# fretscanner4.net
KiCad netlist of a schematic drawn in EAGLE
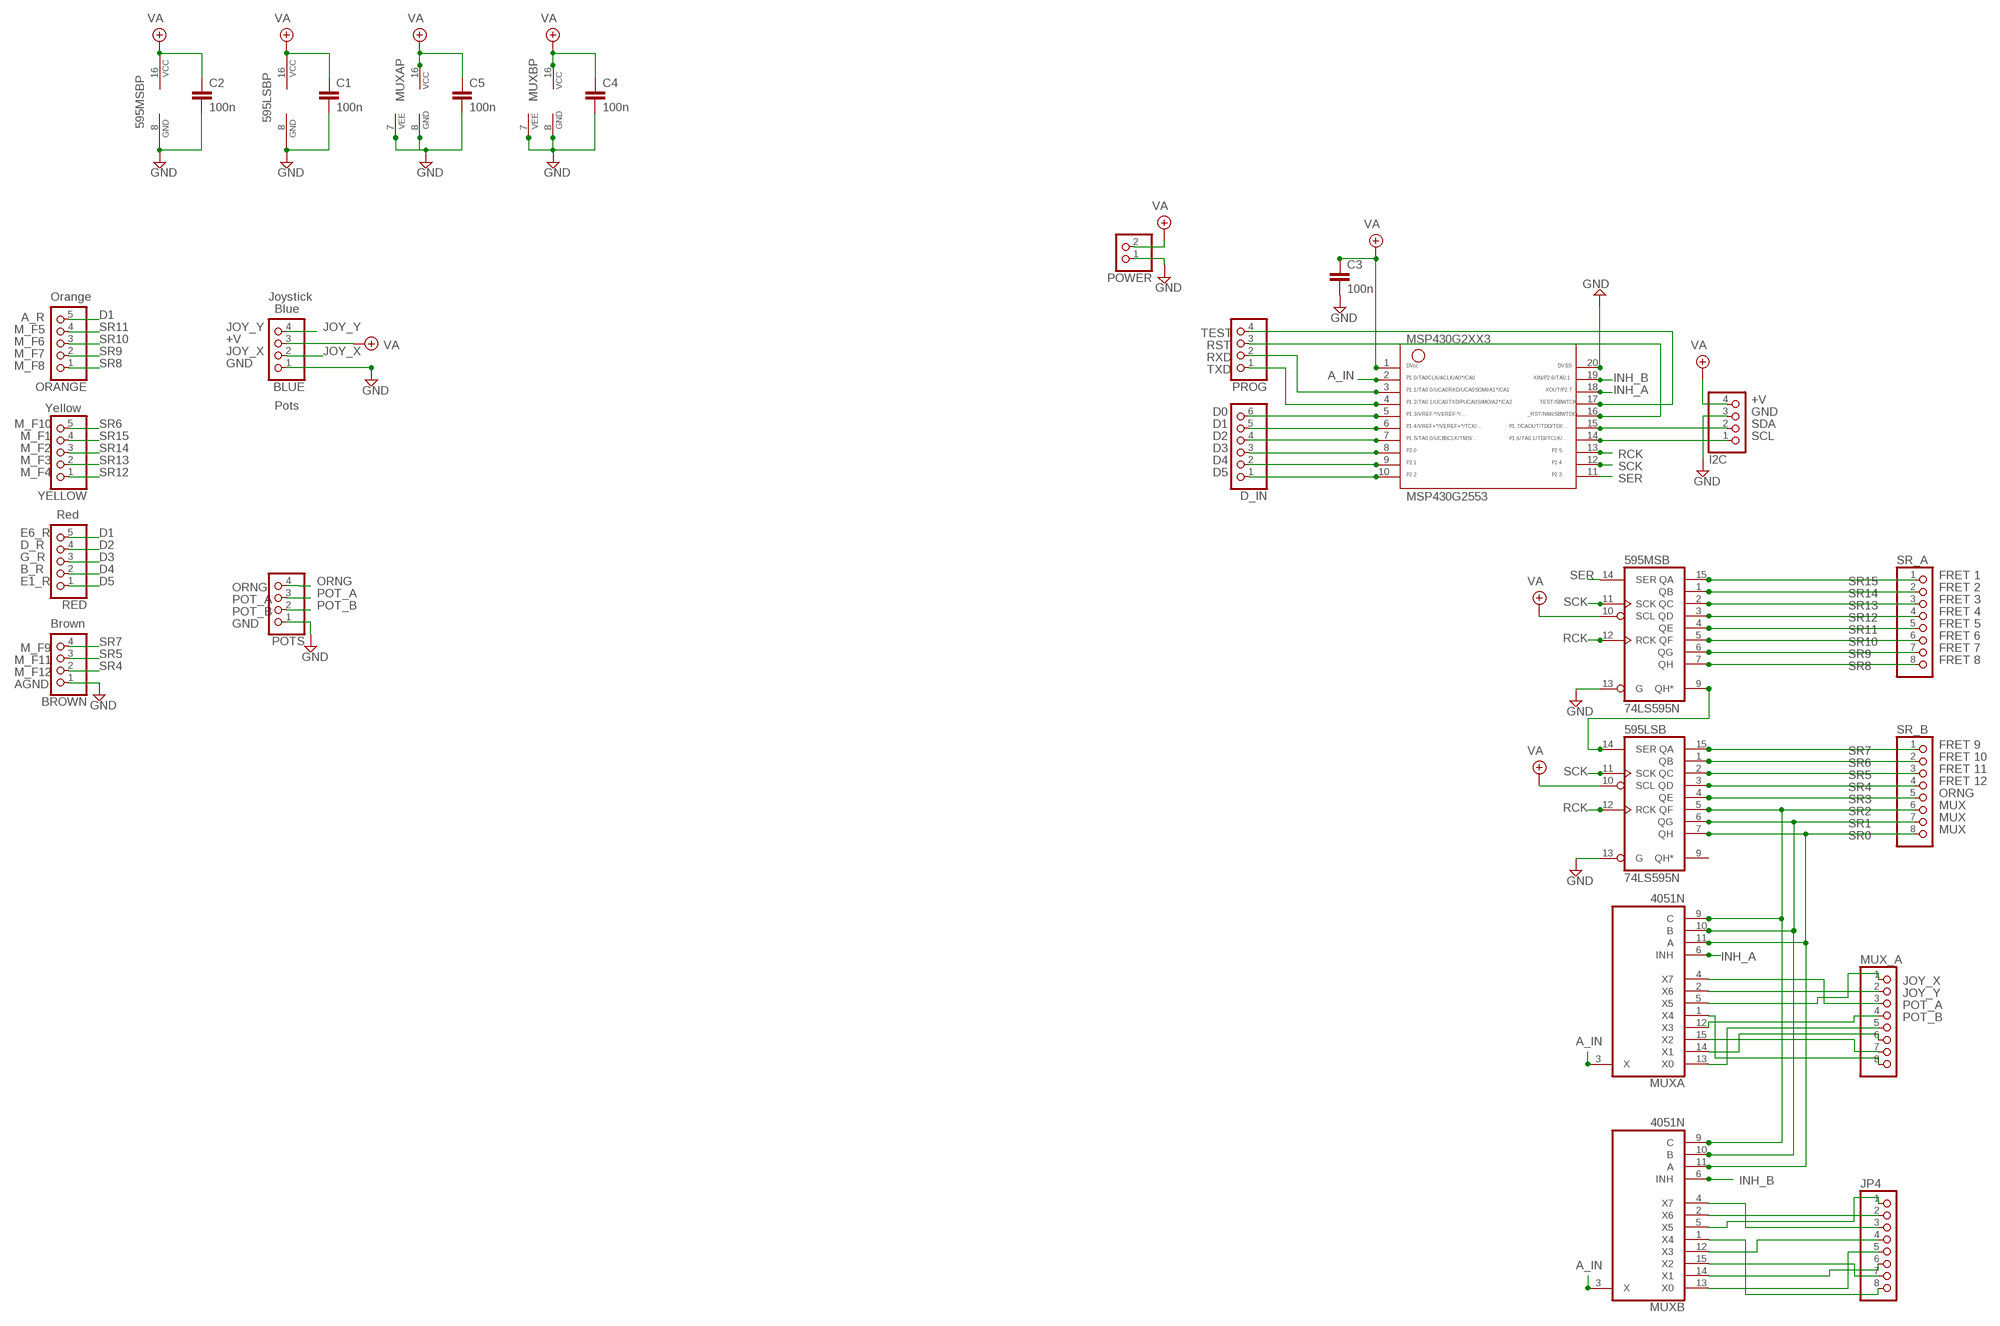
[diagram p0: schematic, sheet 1]

(export (version "E")
  (design (tool "Eeschema 10.0.6"))
  (components
    (comp (ref "595LSB")
      (value "74LS595N")
      (footprint "eagle-import:DIL16")
      (libsource (lib "eagle-import") (part "74595NLS"))
    )
    (comp (ref "595MSB")
      (value "74LS595N")
      (footprint "eagle-import:DIL16")
      (libsource (lib "eagle-import") (part "74595NLS"))
    )
    (comp (ref "BLUE")
      (value "PINHD-1X4")
      (footprint "eagle-import:1X04")
      (libsource (lib "eagle-import") (part "PINHD-1X4"))
    )
    (comp (ref "BROWN")
      (value "PINHD-1X4")
      (footprint "eagle-import:1X04")
      (libsource (lib "eagle-import") (part "PINHD-1X4"))
    )
    (comp (ref "C1")
      (value "100n")
      (footprint "eagle-import:050X030_050_3")
      (libsource (lib "eagle-import") (part "050X030_050"))
    )
    (comp (ref "C2")
      (value "100n")
      (footprint "eagle-import:050X030_050_3")
      (libsource (lib "eagle-import") (part "050X030_050"))
    )
    (comp (ref "C3")
      (value "100n")
      (footprint "eagle-import:050X030_050_3")
      (libsource (lib "eagle-import") (part "050X030_050"))
    )
    (comp (ref "C4")
      (value "100n")
      (footprint "eagle-import:050X030_050_3")
      (libsource (lib "eagle-import") (part "050X030_050"))
    )
    (comp (ref "C5")
      (value "100n")
      (footprint "eagle-import:050X030_050_3")
      (libsource (lib "eagle-import") (part "050X030_050"))
    )
    (comp (ref "D_IN")
      (value "PINHD-1X6")
      (footprint "eagle-import:1X06")
      (libsource (lib "eagle-import") (part "PINHD-1X6"))
    )
    (comp (ref "I2C")
      (value "PINHD-1X4")
      (footprint "eagle-import:1X04")
      (libsource (lib "eagle-import") (part "PINHD-1X4"))
    )
    (comp (ref "JP4")
      (value "PINHD-1X8")
      (footprint "eagle-import:1X08")
      (libsource (lib "eagle-import") (part "PINHD-1X8"))
    )
    (comp (ref "MSP430G2553")
      (value "G2XX3---N20")
      (footprint "eagle-import:N20")
      (libsource (lib "eagle-import") (part "G2XX3---N20"))
    )
    (comp (ref "MUXA")
      (value "4051N")
      (footprint "eagle-import:DIL16")
      (libsource (lib "eagle-import") (part "4051N"))
    )
    (comp (ref "MUXB")
      (value "4051N")
      (footprint "eagle-import:DIL16")
      (libsource (lib "eagle-import") (part "4051N"))
    )
    (comp (ref "MUX_A")
      (value "PINHD-1X8")
      (footprint "eagle-import:1X08")
      (libsource (lib "eagle-import") (part "PINHD-1X8"))
    )
    (comp (ref "ORANGE")
      (value "PINHD-1X5")
      (footprint "eagle-import:1X05")
      (libsource (lib "eagle-import") (part "PINHD-1X5"))
    )
    (comp (ref "POTS")
      (value "PINHD-1X4")
      (footprint "eagle-import:1X04")
      (libsource (lib "eagle-import") (part "PINHD-1X4"))
    )
    (comp (ref "POWER")
      (value "PINHD-1X2")
      (footprint "eagle-import:1X02")
      (libsource (lib "eagle-import") (part "PINHD-1X2"))
    )
    (comp (ref "PROG")
      (value "PINHD-1X4")
      (footprint "eagle-import:1X04")
      (libsource (lib "eagle-import") (part "PINHD-1X4"))
    )
    (comp (ref "RED")
      (value "PINHD-1X5")
      (footprint "eagle-import:1X05")
      (libsource (lib "eagle-import") (part "PINHD-1X5"))
    )
    (comp (ref "SR_A")
      (value "PINHD-1X8")
      (footprint "eagle-import:1X08")
      (libsource (lib "eagle-import") (part "PINHD-1X8"))
    )
    (comp (ref "SR_B")
      (value "PINHD-1X8")
      (footprint "eagle-import:1X08")
      (libsource (lib "eagle-import") (part "PINHD-1X8"))
    )
    (comp (ref "YELLOW")
      (value "PINHD-1X5")
      (footprint "eagle-import:1X05")
      (libsource (lib "eagle-import") (part "PINHD-1X5"))
    )
  )
  (nets
    (net (code "1") (name "/A_IN") (class "Default")
      (node (ref "MSP430G2553") (pin "2") (pinfunction "2_2") (pintype "bidirectional"))
      (node (ref "MUXA") (pin "3") (pinfunction "X_3") (pintype "bidirectional"))
      (node (ref "MUXB") (pin "3") (pinfunction "X_3") (pintype "bidirectional"))
    )
    (net (code "2") (name "/D0") (class "Default")
      (node (ref "D_IN") (pin "6") (pinfunction "6_6") (pintype "passive"))
      (node (ref "MSP430G2553") (pin "5") (pinfunction "5_5") (pintype "bidirectional"))
    )
    (net (code "3") (name "/D1") (class "Default")
      (node (ref "D_IN") (pin "5") (pinfunction "5_5") (pintype "passive"))
      (node (ref "MSP430G2553") (pin "6") (pinfunction "6_6") (pintype "bidirectional"))
      (node (ref "ORANGE") (pin "5") (pinfunction "5_5") (pintype "passive"))
      (node (ref "RED") (pin "5") (pinfunction "5_5") (pintype "passive"))
    )
    (net (code "4") (name "/D2") (class "Default")
      (node (ref "D_IN") (pin "4") (pinfunction "4_4") (pintype "passive"))
      (node (ref "MSP430G2553") (pin "7") (pinfunction "7_7") (pintype "bidirectional"))
      (node (ref "RED") (pin "4") (pinfunction "4_4") (pintype "passive"))
    )
    (net (code "5") (name "/D3") (class "Default")
      (node (ref "D_IN") (pin "3") (pinfunction "3_3") (pintype "passive"))
      (node (ref "MSP430G2553") (pin "8") (pinfunction "8_8") (pintype "bidirectional"))
      (node (ref "RED") (pin "3") (pinfunction "3_3") (pintype "passive"))
    )
    (net (code "6") (name "/D4") (class "Default")
      (node (ref "D_IN") (pin "2") (pinfunction "2_2") (pintype "passive"))
      (node (ref "MSP430G2553") (pin "9") (pinfunction "9_9") (pintype "bidirectional"))
      (node (ref "RED") (pin "2") (pinfunction "2_2") (pintype "passive"))
    )
    (net (code "7") (name "/D5") (class "Default")
      (node (ref "D_IN") (pin "1") (pinfunction "1_1") (pintype "passive"))
      (node (ref "MSP430G2553") (pin "10") (pinfunction "10_10") (pintype "bidirectional"))
      (node (ref "RED") (pin "1") (pinfunction "1_1") (pintype "passive"))
    )
    (net (code "8") (name "/INH_A") (class "Default")
      (node (ref "MSP430G2553") (pin "18") (pinfunction "18_18") (pintype "bidirectional"))
      (node (ref "MUXA") (pin "6") (pinfunction "INH_6") (pintype "input"))
    )
    (net (code "9") (name "/INH_B") (class "Default")
      (node (ref "MSP430G2553") (pin "19") (pinfunction "19_19") (pintype "bidirectional"))
      (node (ref "MUXB") (pin "6") (pinfunction "INH_6") (pintype "input"))
    )
    (net (code "10") (name "/JOY_X") (class "Default")
      (node (ref "BLUE") (pin "2") (pinfunction "2_2") (pintype "passive"))
      (node (ref "MUXA") (pin "5") (pinfunction "X5_5") (pintype "bidirectional"))
      (node (ref "MUX_A") (pin "1") (pinfunction "1_1") (pintype "passive"))
    )
    (net (code "11") (name "/JOY_Y") (class "Default")
      (node (ref "BLUE") (pin "4") (pinfunction "4_4") (pintype "passive"))
      (node (ref "MUXA") (pin "2") (pinfunction "X6_2") (pintype "bidirectional"))
      (node (ref "MUX_A") (pin "2") (pinfunction "2_2") (pintype "passive"))
    )
    (net (code "12") (name "/ORNG") (class "Default")
      (node (ref "POTS") (pin "4") (pinfunction "4_4") (pintype "passive"))
    )
    (net (code "13") (name "/POT_A") (class "Default")
      (node (ref "MUXA") (pin "4") (pinfunction "X7_4") (pintype "bidirectional"))
      (node (ref "MUX_A") (pin "3") (pinfunction "3_3") (pintype "passive"))
      (node (ref "POTS") (pin "3") (pinfunction "3_3") (pintype "passive"))
    )
    (net (code "14") (name "/POT_B") (class "Default")
      (node (ref "MUXA") (pin "12") (pinfunction "X3_12") (pintype "bidirectional"))
      (node (ref "MUX_A") (pin "4") (pinfunction "4_4") (pintype "passive"))
      (node (ref "POTS") (pin "2") (pinfunction "2_2") (pintype "passive"))
    )
    (net (code "15") (name "/RCK") (class "Default")
      (node (ref "595LSB") (pin "12") (pinfunction "RCK_12") (pintype "input"))
      (node (ref "595MSB") (pin "12") (pinfunction "RCK_12") (pintype "input"))
      (node (ref "MSP430G2553") (pin "13") (pinfunction "13_13") (pintype "bidirectional"))
    )
    (net (code "16") (name "/SCK") (class "Default")
      (node (ref "595LSB") (pin "11") (pinfunction "SCK_11") (pintype "input"))
      (node (ref "595MSB") (pin "11") (pinfunction "SCK_11") (pintype "input"))
      (node (ref "MSP430G2553") (pin "12") (pinfunction "12_12") (pintype "bidirectional"))
    )
    (net (code "17") (name "/SER") (class "Default")
      (node (ref "595MSB") (pin "14") (pinfunction "SER_14") (pintype "input"))
      (node (ref "MSP430G2553") (pin "11") (pinfunction "11_11") (pintype "bidirectional"))
    )
    (net (code "18") (name "/SR0") (class "Default")
      (node (ref "595LSB") (pin "7") (pinfunction "QH_7") (pintype "tri_state"))
      (node (ref "MUXA") (pin "11") (pinfunction "A_11") (pintype "input"))
      (node (ref "MUXB") (pin "11") (pinfunction "A_11") (pintype "input"))
      (node (ref "SR_B") (pin "8") (pinfunction "8_8") (pintype "passive"))
    )
    (net (code "19") (name "/SR1") (class "Default")
      (node (ref "595LSB") (pin "6") (pinfunction "QG_6") (pintype "tri_state"))
      (node (ref "MUXA") (pin "10") (pinfunction "B_10") (pintype "input"))
      (node (ref "MUXB") (pin "10") (pinfunction "B_10") (pintype "input"))
      (node (ref "SR_B") (pin "7") (pinfunction "7_7") (pintype "passive"))
    )
    (net (code "20") (name "/SR2") (class "Default")
      (node (ref "595LSB") (pin "5") (pinfunction "QF_5") (pintype "tri_state"))
      (node (ref "MUXA") (pin "9") (pinfunction "C_9") (pintype "input"))
      (node (ref "MUXB") (pin "9") (pinfunction "C_9") (pintype "input"))
      (node (ref "SR_B") (pin "6") (pinfunction "6_6") (pintype "passive"))
    )
    (net (code "21") (name "/SR3") (class "Default")
      (node (ref "595LSB") (pin "4") (pinfunction "QE_4") (pintype "tri_state"))
      (node (ref "SR_B") (pin "5") (pinfunction "5_5") (pintype "passive"))
    )
    (net (code "22") (name "/SR4") (class "Default")
      (node (ref "595LSB") (pin "3") (pinfunction "QD_3") (pintype "tri_state"))
      (node (ref "BROWN") (pin "2") (pinfunction "2_2") (pintype "passive"))
      (node (ref "SR_B") (pin "4") (pinfunction "4_4") (pintype "passive"))
    )
    (net (code "23") (name "/SR5") (class "Default")
      (node (ref "595LSB") (pin "2") (pinfunction "QC_2") (pintype "tri_state"))
      (node (ref "BROWN") (pin "3") (pinfunction "3_3") (pintype "passive"))
      (node (ref "SR_B") (pin "3") (pinfunction "3_3") (pintype "passive"))
    )
    (net (code "24") (name "/SR6") (class "Default")
      (node (ref "595LSB") (pin "1") (pinfunction "QB_1") (pintype "tri_state"))
      (node (ref "SR_B") (pin "2") (pinfunction "2_2") (pintype "passive"))
      (node (ref "YELLOW") (pin "5") (pinfunction "5_5") (pintype "passive"))
    )
    (net (code "25") (name "/SR7") (class "Default")
      (node (ref "595LSB") (pin "15") (pinfunction "QA_15") (pintype "tri_state"))
      (node (ref "BROWN") (pin "4") (pinfunction "4_4") (pintype "passive"))
      (node (ref "SR_B") (pin "1") (pinfunction "1_1") (pintype "passive"))
    )
    (net (code "26") (name "/SR8") (class "Default")
      (node (ref "595MSB") (pin "7") (pinfunction "QH_7") (pintype "tri_state"))
      (node (ref "ORANGE") (pin "1") (pinfunction "1_1") (pintype "passive"))
      (node (ref "SR_A") (pin "8") (pinfunction "8_8") (pintype "passive"))
    )
    (net (code "27") (name "/SR9") (class "Default")
      (node (ref "595MSB") (pin "6") (pinfunction "QG_6") (pintype "tri_state"))
      (node (ref "ORANGE") (pin "2") (pinfunction "2_2") (pintype "passive"))
      (node (ref "SR_A") (pin "7") (pinfunction "7_7") (pintype "passive"))
    )
    (net (code "28") (name "/SR10") (class "Default")
      (node (ref "595MSB") (pin "5") (pinfunction "QF_5") (pintype "tri_state"))
      (node (ref "ORANGE") (pin "3") (pinfunction "3_3") (pintype "passive"))
      (node (ref "SR_A") (pin "6") (pinfunction "6_6") (pintype "passive"))
    )
    (net (code "29") (name "/SR11") (class "Default")
      (node (ref "595MSB") (pin "4") (pinfunction "QE_4") (pintype "tri_state"))
      (node (ref "ORANGE") (pin "4") (pinfunction "4_4") (pintype "passive"))
      (node (ref "SR_A") (pin "5") (pinfunction "5_5") (pintype "passive"))
    )
    (net (code "30") (name "/SR12") (class "Default")
      (node (ref "595MSB") (pin "3") (pinfunction "QD_3") (pintype "tri_state"))
      (node (ref "SR_A") (pin "4") (pinfunction "4_4") (pintype "passive"))
      (node (ref "YELLOW") (pin "1") (pinfunction "1_1") (pintype "passive"))
    )
    (net (code "31") (name "/SR13") (class "Default")
      (node (ref "595MSB") (pin "2") (pinfunction "QC_2") (pintype "tri_state"))
      (node (ref "SR_A") (pin "3") (pinfunction "3_3") (pintype "passive"))
      (node (ref "YELLOW") (pin "2") (pinfunction "2_2") (pintype "passive"))
    )
    (net (code "32") (name "/SR14") (class "Default")
      (node (ref "595MSB") (pin "1") (pinfunction "QB_1") (pintype "tri_state"))
      (node (ref "SR_A") (pin "2") (pinfunction "2_2") (pintype "passive"))
      (node (ref "YELLOW") (pin "3") (pinfunction "3_3") (pintype "passive"))
    )
    (net (code "33") (name "/SR15") (class "Default")
      (node (ref "595MSB") (pin "15") (pinfunction "QA_15") (pintype "tri_state"))
      (node (ref "SR_A") (pin "1") (pinfunction "1_1") (pintype "passive"))
      (node (ref "YELLOW") (pin "4") (pinfunction "4_4") (pintype "passive"))
    )
    (net (code "34") (name "GND") (class "Default")
      (node (ref "595LSB") (pin "13") (pinfunction "G_13") (pintype "input"))
      (node (ref "595LSB") (pin "8") (pinfunction "GND_8") (pintype "power_in"))
      (node (ref "595MSB") (pin "13") (pinfunction "G_13") (pintype "input"))
      (node (ref "595MSB") (pin "8") (pinfunction "GND_8") (pintype "power_in"))
      (node (ref "BLUE") (pin "1") (pinfunction "1_1") (pintype "passive"))
      (node (ref "BROWN") (pin "1") (pinfunction "1_1") (pintype "passive"))
      (node (ref "C1") (pin "2") (pinfunction "2_2") (pintype "passive"))
      (node (ref "C2") (pin "2") (pinfunction "2_2") (pintype "passive"))
      (node (ref "C3") (pin "2") (pinfunction "2_2") (pintype "passive"))
      (node (ref "C4") (pin "2") (pinfunction "2_2") (pintype "passive"))
      (node (ref "C5") (pin "2") (pinfunction "2_2") (pintype "passive"))
      (node (ref "I2C") (pin "3") (pinfunction "3_3") (pintype "passive"))
      (node (ref "MSP430G2553") (pin "20") (pinfunction "20_20") (pintype "bidirectional"))
      (node (ref "MUXA") (pin "7") (pinfunction "VEE_7") (pintype "power_in"))
      (node (ref "MUXA") (pin "8") (pinfunction "GND_8") (pintype "power_in"))
      (node (ref "MUXB") (pin "7") (pinfunction "VEE_7") (pintype "power_in"))
      (node (ref "MUXB") (pin "8") (pinfunction "GND_8") (pintype "power_in"))
      (node (ref "POTS") (pin "1") (pinfunction "1_1") (pintype "passive"))
      (node (ref "POWER") (pin "1") (pinfunction "1_1") (pintype "passive"))
    )
    (net (code "35") (name "Net-(595LSBA-SER)") (class "Default")
      (node (ref "595LSB") (pin "14") (pinfunction "SER_14") (pintype "input"))
      (node (ref "595MSB") (pin "9") (pinfunction "QH*_9") (pintype "tri_state"))
    )
    (net (code "36") (name "Net-(I2C-Pad1)") (class "Default")
      (node (ref "I2C") (pin "1") (pinfunction "1_1") (pintype "passive"))
      (node (ref "MSP430G2553") (pin "14") (pinfunction "14_14") (pintype "bidirectional"))
    )
    (net (code "37") (name "Net-(I2C-Pad2)") (class "Default")
      (node (ref "I2C") (pin "2") (pinfunction "2_2") (pintype "passive"))
      (node (ref "MSP430G2553") (pin "15") (pinfunction "15_15") (pintype "bidirectional"))
    )
    (net (code "38") (name "Net-(MSP430G2553-Pad3)") (class "Default")
      (node (ref "MSP430G2553") (pin "3") (pinfunction "3_3") (pintype "bidirectional"))
      (node (ref "PROG") (pin "2") (pinfunction "2_2") (pintype "passive"))
    )
    (net (code "39") (name "Net-(MSP430G2553-Pad4)") (class "Default")
      (node (ref "MSP430G2553") (pin "4") (pinfunction "4_4") (pintype "bidirectional"))
      (node (ref "PROG") (pin "1") (pinfunction "1_1") (pintype "passive"))
    )
    (net (code "40") (name "Net-(MSP430G2553-Pad16)") (class "Default")
      (node (ref "MSP430G2553") (pin "16") (pinfunction "16_16") (pintype "bidirectional"))
      (node (ref "PROG") (pin "3") (pinfunction "3_3") (pintype "passive"))
    )
    (net (code "41") (name "Net-(MSP430G2553-Pad17)") (class "Default")
      (node (ref "MSP430G2553") (pin "17") (pinfunction "17_17") (pintype "bidirectional"))
      (node (ref "PROG") (pin "4") (pinfunction "4_4") (pintype "passive"))
    )
    (net (code "42") (name "Net-(MUXAA-X0)") (class "Default")
      (node (ref "MUXA") (pin "13") (pinfunction "X0_13") (pintype "bidirectional"))
      (node (ref "MUX_A") (pin "5") (pinfunction "5_5") (pintype "passive"))
    )
    (net (code "43") (name "Net-(MUXAA-X1)") (class "Default")
      (node (ref "MUXA") (pin "14") (pinfunction "X1_14") (pintype "bidirectional"))
      (node (ref "MUX_A") (pin "6") (pinfunction "6_6") (pintype "passive"))
    )
    (net (code "44") (name "Net-(MUXAA-X2)") (class "Default")
      (node (ref "MUXA") (pin "15") (pinfunction "X2_15") (pintype "bidirectional"))
      (node (ref "MUX_A") (pin "7") (pinfunction "7_7") (pintype "passive"))
    )
    (net (code "45") (name "Net-(MUXAA-X4)") (class "Default")
      (node (ref "MUXA") (pin "1") (pinfunction "X4_1") (pintype "bidirectional"))
      (node (ref "MUX_A") (pin "8") (pinfunction "8_8") (pintype "passive"))
    )
    (net (code "46") (name "Net-(MUXBA-X0)") (class "Default")
      (node (ref "JP4") (pin "5") (pinfunction "5_5") (pintype "passive"))
      (node (ref "MUXB") (pin "13") (pinfunction "X0_13") (pintype "bidirectional"))
    )
    (net (code "47") (name "Net-(MUXBA-X1)") (class "Default")
      (node (ref "JP4") (pin "6") (pinfunction "6_6") (pintype "passive"))
      (node (ref "MUXB") (pin "14") (pinfunction "X1_14") (pintype "bidirectional"))
    )
    (net (code "48") (name "Net-(MUXBA-X2)") (class "Default")
      (node (ref "JP4") (pin "7") (pinfunction "7_7") (pintype "passive"))
      (node (ref "MUXB") (pin "15") (pinfunction "X2_15") (pintype "bidirectional"))
    )
    (net (code "49") (name "Net-(MUXBA-X3)") (class "Default")
      (node (ref "JP4") (pin "4") (pinfunction "4_4") (pintype "passive"))
      (node (ref "MUXB") (pin "12") (pinfunction "X3_12") (pintype "bidirectional"))
    )
    (net (code "50") (name "Net-(MUXBA-X4)") (class "Default")
      (node (ref "JP4") (pin "8") (pinfunction "8_8") (pintype "passive"))
      (node (ref "MUXB") (pin "1") (pinfunction "X4_1") (pintype "bidirectional"))
    )
    (net (code "51") (name "Net-(MUXBA-X5)") (class "Default")
      (node (ref "JP4") (pin "1") (pinfunction "1_1") (pintype "passive"))
      (node (ref "MUXB") (pin "5") (pinfunction "X5_5") (pintype "bidirectional"))
    )
    (net (code "52") (name "Net-(MUXBA-X6)") (class "Default")
      (node (ref "JP4") (pin "2") (pinfunction "2_2") (pintype "passive"))
      (node (ref "MUXB") (pin "2") (pinfunction "X6_2") (pintype "bidirectional"))
    )
    (net (code "53") (name "Net-(MUXBA-X7)") (class "Default")
      (node (ref "JP4") (pin "3") (pinfunction "3_3") (pintype "passive"))
      (node (ref "MUXB") (pin "4") (pinfunction "X7_4") (pintype "bidirectional"))
    )
    (net (code "54") (name "VA") (class "Default")
      (node (ref "595LSB") (pin "10") (pinfunction "SCL_10") (pintype "input"))
      (node (ref "595LSB") (pin "16") (pinfunction "VCC_16") (pintype "power_in"))
      (node (ref "595MSB") (pin "10") (pinfunction "SCL_10") (pintype "input"))
      (node (ref "595MSB") (pin "16") (pinfunction "VCC_16") (pintype "power_in"))
      (node (ref "BLUE") (pin "3") (pinfunction "3_3") (pintype "passive"))
      (node (ref "C1") (pin "1") (pinfunction "1_1") (pintype "passive"))
      (node (ref "C2") (pin "1") (pinfunction "1_1") (pintype "passive"))
      (node (ref "C3") (pin "1") (pinfunction "1_1") (pintype "passive"))
      (node (ref "C4") (pin "1") (pinfunction "1_1") (pintype "passive"))
      (node (ref "C5") (pin "1") (pinfunction "1_1") (pintype "passive"))
      (node (ref "I2C") (pin "4") (pinfunction "4_4") (pintype "passive"))
      (node (ref "MSP430G2553") (pin "1") (pinfunction "1_1") (pintype "bidirectional"))
      (node (ref "MUXA") (pin "16") (pinfunction "VCC_16") (pintype "power_in"))
      (node (ref "MUXB") (pin "16") (pinfunction "VCC_16") (pintype "power_in"))
      (node (ref "POWER") (pin "2") (pinfunction "2_2") (pintype "passive"))
    )
    (net (code "55") (name "unconnected-(595LSBA-QH*-Pad9)") (class "Default")
      (node (ref "595LSB") (pin "9") (pinfunction "QH*_9") (pintype "tri_state"))
    )
  )
)
